# MAR.net
KiCad netlist of a schematic drawn in EAGLE
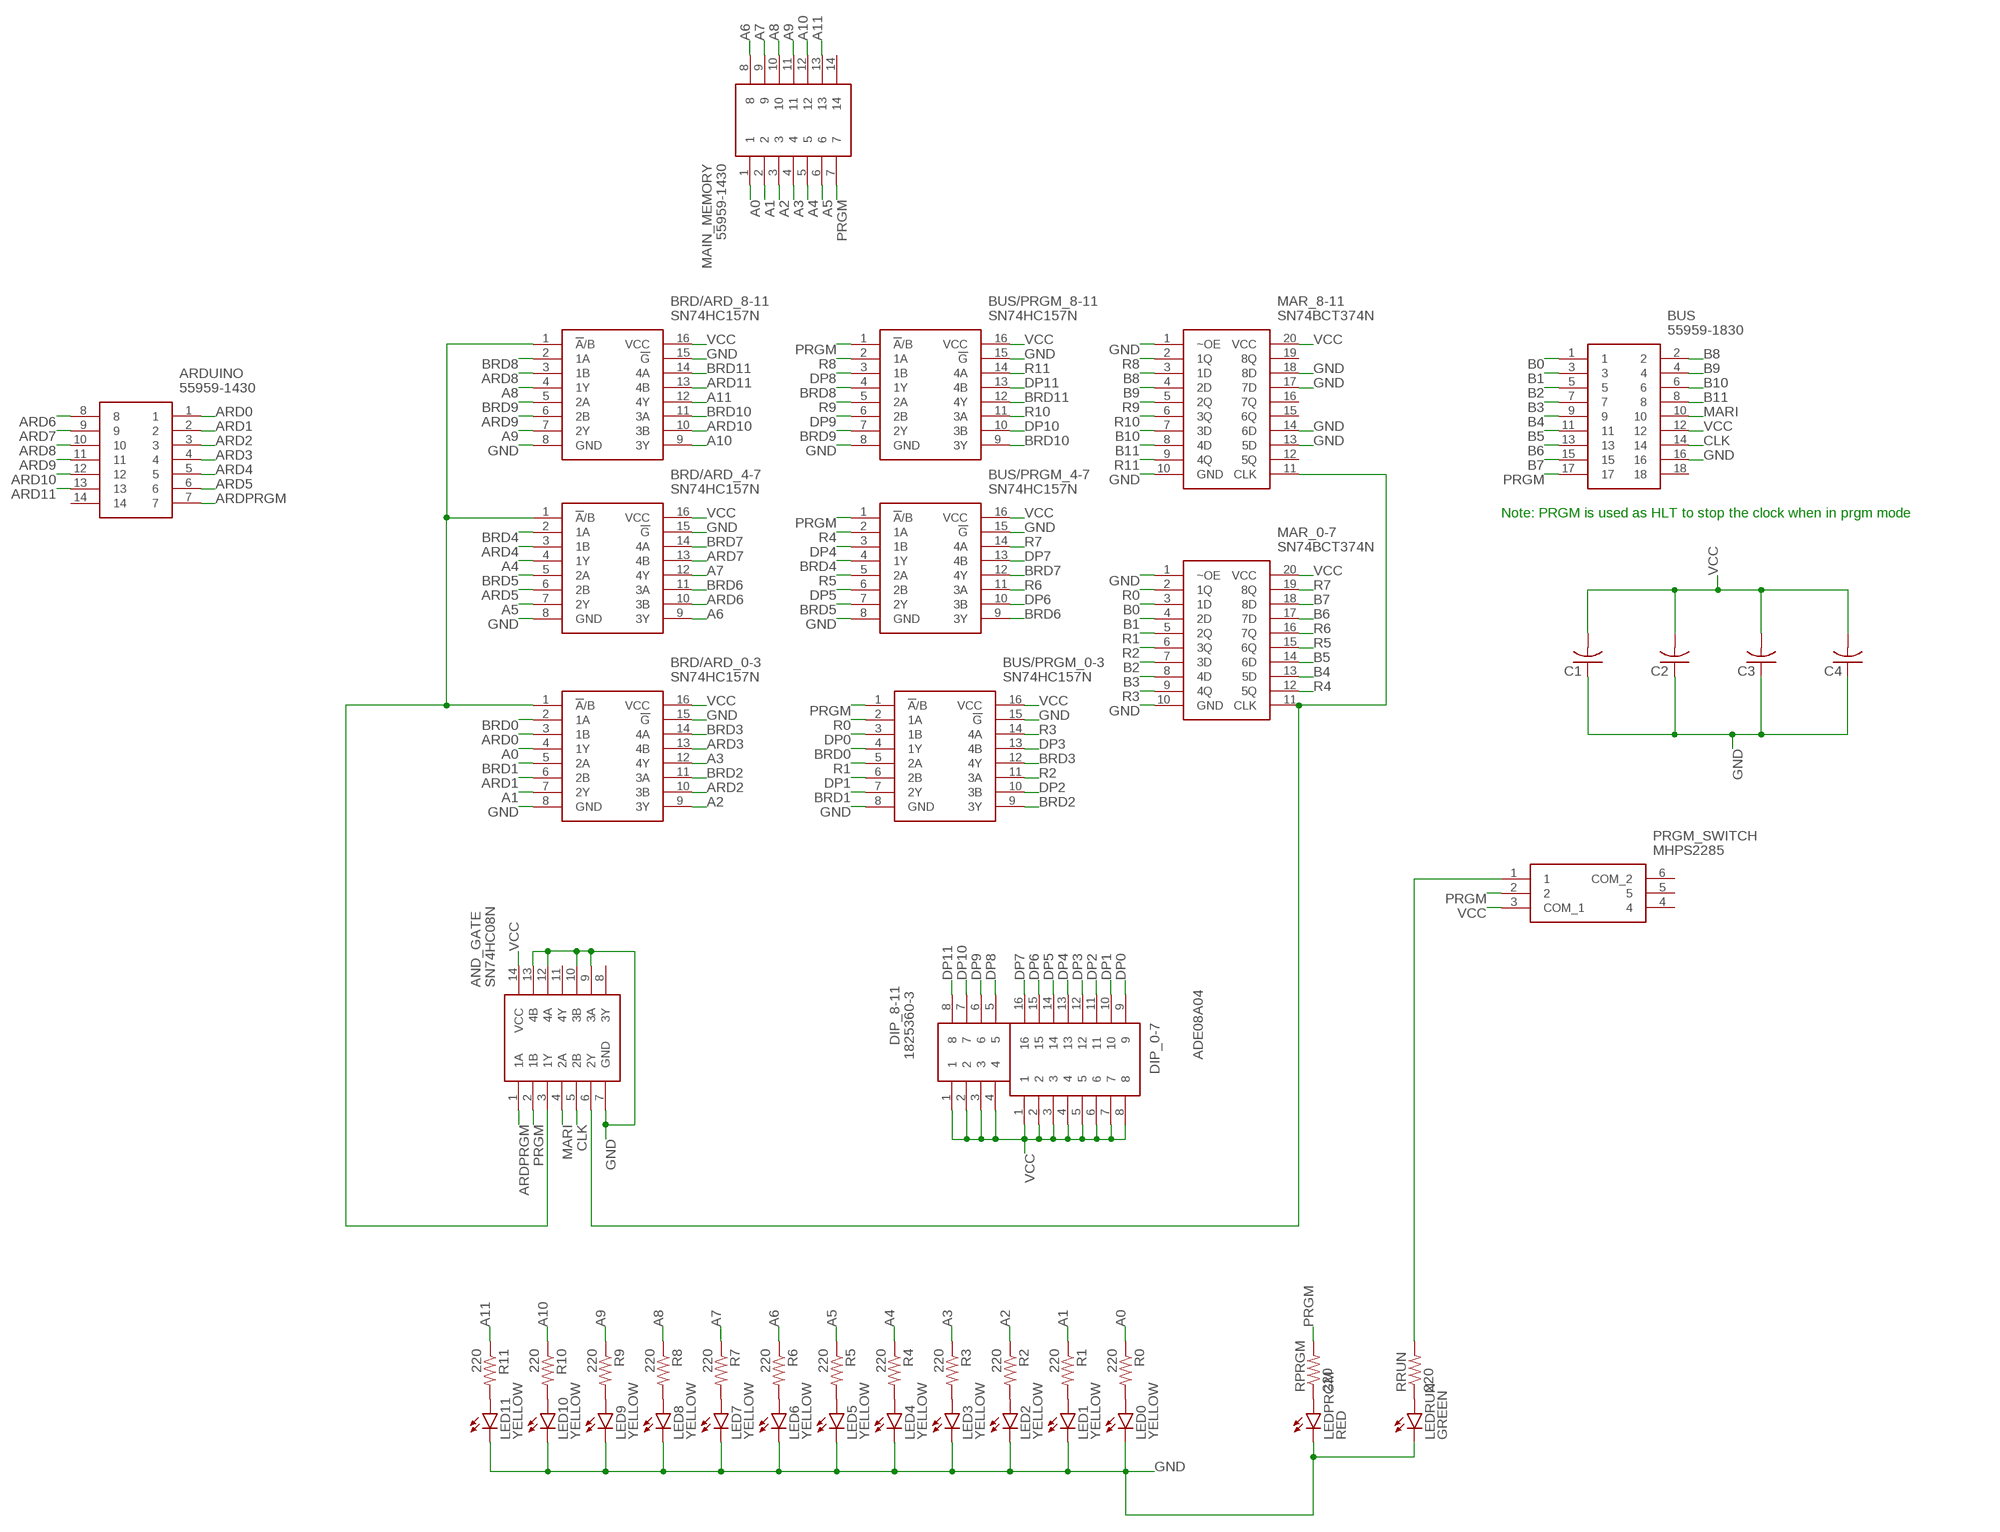
[diagram p0: schematic, sheet 1]

(export (version "E")
  (design (tool "Eeschema 10.0.6"))
  (components
    (comp (ref "AND_GATE")
      (value "SN74HC08N")
      (footprint "eagle-import:DIP794W53P254L1930H508Q14N")
      (fields (field (name "MOUSER_PART_NUMBER") "595-SN74HC08N"))
      (libsource (lib "eagle-import") (part "SN74HC08N"))
    )
    (comp (ref "ARDUINO")
      (value "55959-1430")
      (footprint "eagle-import:559591430")
      (fields (field (name "MOUSER_PART_NUMBER") "538-55959-1430"))
      (libsource (lib "eagle-import") (part "55959-1430"))
    )
    (comp (ref "BRD/ARD_0-3")
      (value "SN74HC157N")
      (footprint "eagle-import:DIP794W53P254L1930H508Q16N")
      (fields (field (name "MOUSER_PART_NUMBER") "595-SN74HC157N"))
      (libsource (lib "eagle-import") (part "SN74HC157N"))
    )
    (comp (ref "BRD/ARD_4-7")
      (value "SN74HC157N")
      (footprint "eagle-import:DIP794W53P254L1930H508Q16N")
      (fields (field (name "MOUSER_PART_NUMBER") "595-SN74HC157N"))
      (libsource (lib "eagle-import") (part "SN74HC157N"))
    )
    (comp (ref "BRD/ARD_8-11")
      (value "SN74HC157N")
      (footprint "eagle-import:DIP794W53P254L1930H508Q16N")
      (fields (field (name "MOUSER_PART_NUMBER") "595-SN74HC157N"))
      (libsource (lib "eagle-import") (part "SN74HC157N"))
    )
    (comp (ref "BUS")
      (value "55959-1830")
      (footprint "eagle-import:SHDR18W65P250X200_2X9_2140X140")
      (fields (field (name "MOUSER_PART_NUMBER") "538-55959-1830"))
      (libsource (lib "eagle-import") (part "55959-1830"))
    )
    (comp (ref "BUS/PRGM_0-3")
      (value "SN74HC157N")
      (footprint "eagle-import:DIP794W53P254L1930H508Q16N")
      (fields (field (name "MOUSER_PART_NUMBER") "595-SN74HC157N"))
      (libsource (lib "eagle-import") (part "SN74HC157N"))
    )
    (comp (ref "BUS/PRGM_4-7")
      (value "SN74HC157N")
      (footprint "eagle-import:DIP794W53P254L1930H508Q16N")
      (fields (field (name "MOUSER_PART_NUMBER") "595-SN74HC157N"))
      (libsource (lib "eagle-import") (part "SN74HC157N"))
    )
    (comp (ref "BUS/PRGM_8-11")
      (value "SN74HC157N")
      (footprint "eagle-import:DIP794W53P254L1930H508Q16N")
      (fields (field (name "MOUSER_PART_NUMBER") "595-SN74HC157N"))
      (libsource (lib "eagle-import") (part "SN74HC157N"))
    )
    (comp (ref "C1")
      (value "C-US025-024X044")
      (footprint "eagle-import:C025-024X044")
      (libsource (lib "eagle-import") (part "C-US025-024X044"))
    )
    (comp (ref "C2")
      (value "C-US025-024X044")
      (footprint "eagle-import:C025-024X044")
      (libsource (lib "eagle-import") (part "C-US025-024X044"))
    )
    (comp (ref "C3")
      (value "C-US025-024X044")
      (footprint "eagle-import:C025-024X044")
      (libsource (lib "eagle-import") (part "C-US025-024X044"))
    )
    (comp (ref "C4")
      (value "C-US025-024X044")
      (footprint "eagle-import:C025-024X044")
      (libsource (lib "eagle-import") (part "C-US025-024X044"))
    )
    (comp (ref "DIP_0-7")
      (value "ADE08A04")
      (footprint "eagle-import:DIP810W60P254L2225H590Q16N")
      (fields (field (name "MOUSER_PART_NUMBER") "506-ADE08A04"))
      (libsource (lib "eagle-import") (part "ADE08A04"))
    )
    (comp (ref "DIP_8-11")
      (value "1825360-3")
      (footprint "eagle-import:DIP813W61P254L1209H351Q8N")
      (fields (field (name "MOUSER_PART_NUMBER") "506-1825360-3"))
      (libsource (lib "eagle-import") (part "1825360-3"))
    )
    (comp (ref "LED0")
      (value "YELLOW")
      (footprint "eagle-import:LED3MM")
      (libsource (lib "eagle-import") (part "LED3MM"))
    )
    (comp (ref "LED1")
      (value "YELLOW")
      (footprint "eagle-import:LED3MM")
      (libsource (lib "eagle-import") (part "LED3MM"))
    )
    (comp (ref "LED2")
      (value "YELLOW")
      (footprint "eagle-import:LED3MM")
      (libsource (lib "eagle-import") (part "LED3MM"))
    )
    (comp (ref "LED3")
      (value "YELLOW")
      (footprint "eagle-import:LED3MM")
      (libsource (lib "eagle-import") (part "LED3MM"))
    )
    (comp (ref "LED4")
      (value "YELLOW")
      (footprint "eagle-import:LED3MM")
      (libsource (lib "eagle-import") (part "LED3MM"))
    )
    (comp (ref "LED5")
      (value "YELLOW")
      (footprint "eagle-import:LED3MM")
      (libsource (lib "eagle-import") (part "LED3MM"))
    )
    (comp (ref "LED6")
      (value "YELLOW")
      (footprint "eagle-import:LED3MM")
      (libsource (lib "eagle-import") (part "LED3MM"))
    )
    (comp (ref "LED7")
      (value "YELLOW")
      (footprint "eagle-import:LED3MM")
      (libsource (lib "eagle-import") (part "LED3MM"))
    )
    (comp (ref "LED8")
      (value "YELLOW")
      (footprint "eagle-import:LED3MM")
      (libsource (lib "eagle-import") (part "LED3MM"))
    )
    (comp (ref "LED9")
      (value "YELLOW")
      (footprint "eagle-import:LED3MM")
      (libsource (lib "eagle-import") (part "LED3MM"))
    )
    (comp (ref "LED10")
      (value "YELLOW")
      (footprint "eagle-import:LED3MM")
      (libsource (lib "eagle-import") (part "LED3MM"))
    )
    (comp (ref "LED11")
      (value "YELLOW")
      (footprint "eagle-import:LED3MM")
      (libsource (lib "eagle-import") (part "LED3MM"))
    )
    (comp (ref "LEDPRGM")
      (value "RED")
      (footprint "eagle-import:LED3MM")
      (libsource (lib "eagle-import") (part "LED3MM"))
    )
    (comp (ref "LEDRUN")
      (value "GREEN")
      (footprint "eagle-import:LED3MM")
      (libsource (lib "eagle-import") (part "LED3MM"))
    )
    (comp (ref "MAIN_MEMORY")
      (value "55959-1430")
      (footprint "eagle-import:559591430")
      (fields (field (name "MOUSER_PART_NUMBER") "538-55959-1430"))
      (libsource (lib "eagle-import") (part "55959-1430"))
    )
    (comp (ref "MAR_0-7")
      (value "SN74BCT374N")
      (footprint "eagle-import:DIP254P762X508-20")
      (fields (field (name "MOUSER_PART_NUMBER") "595-SN74BCT374N"))
      (libsource (lib "eagle-import") (part "SN74BCT374N"))
    )
    (comp (ref "MAR_8-11")
      (value "SN74BCT374N")
      (footprint "eagle-import:DIP254P762X508-20")
      (fields (field (name "MOUSER_PART_NUMBER") "595-SN74BCT374N"))
      (libsource (lib "eagle-import") (part "SN74BCT374N"))
    )
    (comp (ref "PRGM_SWITCH")
      (value "MHPS2285")
      (footprint "eagle-import:MHPS2285")
      (fields (field (name "MOUSER_PART_NUMBER") "642-MHPS2285"))
      (libsource (lib "eagle-import") (part "MHPS2285"))
    )
    (comp (ref "R0")
      (value "220")
      (footprint "eagle-import:0204_7")
      (libsource (lib "eagle-import") (part "R-US_0204/7"))
    )
    (comp (ref "R1")
      (value "220")
      (footprint "eagle-import:0204_7")
      (libsource (lib "eagle-import") (part "R-US_0204/7"))
    )
    (comp (ref "R2")
      (value "220")
      (footprint "eagle-import:0204_7")
      (libsource (lib "eagle-import") (part "R-US_0204/7"))
    )
    (comp (ref "R3")
      (value "220")
      (footprint "eagle-import:0204_7")
      (libsource (lib "eagle-import") (part "R-US_0204/7"))
    )
    (comp (ref "R4")
      (value "220")
      (footprint "eagle-import:0204_7")
      (libsource (lib "eagle-import") (part "R-US_0204/7"))
    )
    (comp (ref "R5")
      (value "220")
      (footprint "eagle-import:0204_7")
      (libsource (lib "eagle-import") (part "R-US_0204/7"))
    )
    (comp (ref "R6")
      (value "220")
      (footprint "eagle-import:0204_7")
      (libsource (lib "eagle-import") (part "R-US_0204/7"))
    )
    (comp (ref "R7")
      (value "220")
      (footprint "eagle-import:0204_7")
      (libsource (lib "eagle-import") (part "R-US_0204/7"))
    )
    (comp (ref "R8")
      (value "220")
      (footprint "eagle-import:0204_7")
      (libsource (lib "eagle-import") (part "R-US_0204/7"))
    )
    (comp (ref "R9")
      (value "220")
      (footprint "eagle-import:0204_7")
      (libsource (lib "eagle-import") (part "R-US_0204/7"))
    )
    (comp (ref "R10")
      (value "220")
      (footprint "eagle-import:0204_7")
      (libsource (lib "eagle-import") (part "R-US_0204/7"))
    )
    (comp (ref "R11")
      (value "220")
      (footprint "eagle-import:0204_7")
      (libsource (lib "eagle-import") (part "R-US_0204/7"))
    )
    (comp (ref "RPRGM")
      (value "220")
      (footprint "eagle-import:0204_7")
      (libsource (lib "eagle-import") (part "R-US_0204/7"))
    )
    (comp (ref "RRUN")
      (value "220")
      (footprint "eagle-import:0204_7")
      (libsource (lib "eagle-import") (part "R-US_0204/7"))
    )
  )
  (nets
    (net (code "1") (name "/A0") (class "Default")
      (node (ref "BRD/ARD_0-3") (pin "4") (pinfunction "1Y_4") (pintype "bidirectional"))
      (node (ref "MAIN_MEMORY") (pin "1") (pinfunction "1_1") (pintype "bidirectional"))
      (node (ref "R0") (pin "1") (pinfunction "1_1") (pintype "passive"))
    )
    (net (code "2") (name "/A1") (class "Default")
      (node (ref "BRD/ARD_0-3") (pin "7") (pinfunction "2Y_7") (pintype "bidirectional"))
      (node (ref "MAIN_MEMORY") (pin "2") (pinfunction "2_2") (pintype "bidirectional"))
      (node (ref "R1") (pin "1") (pinfunction "1_1") (pintype "passive"))
    )
    (net (code "3") (name "/A2") (class "Default")
      (node (ref "BRD/ARD_0-3") (pin "9") (pinfunction "3Y_9") (pintype "bidirectional"))
      (node (ref "MAIN_MEMORY") (pin "3") (pinfunction "3_3") (pintype "bidirectional"))
      (node (ref "R2") (pin "1") (pinfunction "1_1") (pintype "passive"))
    )
    (net (code "4") (name "/A3") (class "Default")
      (node (ref "BRD/ARD_0-3") (pin "12") (pinfunction "4Y_12") (pintype "bidirectional"))
      (node (ref "MAIN_MEMORY") (pin "4") (pinfunction "4_4") (pintype "bidirectional"))
      (node (ref "R3") (pin "1") (pinfunction "1_1") (pintype "passive"))
    )
    (net (code "5") (name "/A4") (class "Default")
      (node (ref "BRD/ARD_4-7") (pin "4") (pinfunction "1Y_4") (pintype "bidirectional"))
      (node (ref "MAIN_MEMORY") (pin "5") (pinfunction "5_5") (pintype "bidirectional"))
      (node (ref "R4") (pin "1") (pinfunction "1_1") (pintype "passive"))
    )
    (net (code "6") (name "/A5") (class "Default")
      (node (ref "BRD/ARD_4-7") (pin "7") (pinfunction "2Y_7") (pintype "bidirectional"))
      (node (ref "MAIN_MEMORY") (pin "6") (pinfunction "6_6") (pintype "bidirectional"))
      (node (ref "R5") (pin "1") (pinfunction "1_1") (pintype "passive"))
    )
    (net (code "7") (name "/A6") (class "Default")
      (node (ref "BRD/ARD_4-7") (pin "9") (pinfunction "3Y_9") (pintype "bidirectional"))
      (node (ref "MAIN_MEMORY") (pin "8") (pinfunction "8_8") (pintype "bidirectional"))
      (node (ref "R6") (pin "1") (pinfunction "1_1") (pintype "passive"))
    )
    (net (code "8") (name "/A7") (class "Default")
      (node (ref "BRD/ARD_4-7") (pin "12") (pinfunction "4Y_12") (pintype "bidirectional"))
      (node (ref "MAIN_MEMORY") (pin "9") (pinfunction "9_9") (pintype "bidirectional"))
      (node (ref "R7") (pin "1") (pinfunction "1_1") (pintype "passive"))
    )
    (net (code "9") (name "/A8") (class "Default")
      (node (ref "BRD/ARD_8-11") (pin "4") (pinfunction "1Y_4") (pintype "bidirectional"))
      (node (ref "MAIN_MEMORY") (pin "10") (pinfunction "10_10") (pintype "bidirectional"))
      (node (ref "R8") (pin "1") (pinfunction "1_1") (pintype "passive"))
    )
    (net (code "10") (name "/A9") (class "Default")
      (node (ref "BRD/ARD_8-11") (pin "7") (pinfunction "2Y_7") (pintype "bidirectional"))
      (node (ref "MAIN_MEMORY") (pin "11") (pinfunction "11_11") (pintype "bidirectional"))
      (node (ref "R9") (pin "1") (pinfunction "1_1") (pintype "passive"))
    )
    (net (code "11") (name "/A10") (class "Default")
      (node (ref "BRD/ARD_8-11") (pin "9") (pinfunction "3Y_9") (pintype "bidirectional"))
      (node (ref "MAIN_MEMORY") (pin "12") (pinfunction "12_12") (pintype "bidirectional"))
      (node (ref "R10") (pin "1") (pinfunction "1_1") (pintype "passive"))
    )
    (net (code "12") (name "/A11") (class "Default")
      (node (ref "BRD/ARD_8-11") (pin "12") (pinfunction "4Y_12") (pintype "bidirectional"))
      (node (ref "MAIN_MEMORY") (pin "13") (pinfunction "13_13") (pintype "bidirectional"))
      (node (ref "R11") (pin "1") (pinfunction "1_1") (pintype "passive"))
    )
    (net (code "13") (name "/ARD0") (class "Default")
      (node (ref "ARDUINO") (pin "1") (pinfunction "1_1") (pintype "bidirectional"))
      (node (ref "BRD/ARD_0-3") (pin "3") (pinfunction "1B_3") (pintype "bidirectional"))
    )
    (net (code "14") (name "/ARD1") (class "Default")
      (node (ref "ARDUINO") (pin "2") (pinfunction "2_2") (pintype "bidirectional"))
      (node (ref "BRD/ARD_0-3") (pin "6") (pinfunction "2B_6") (pintype "bidirectional"))
    )
    (net (code "15") (name "/ARD2") (class "Default")
      (node (ref "ARDUINO") (pin "3") (pinfunction "3_3") (pintype "bidirectional"))
      (node (ref "BRD/ARD_0-3") (pin "10") (pinfunction "3B_10") (pintype "bidirectional"))
    )
    (net (code "16") (name "/ARD3") (class "Default")
      (node (ref "ARDUINO") (pin "4") (pinfunction "4_4") (pintype "bidirectional"))
      (node (ref "BRD/ARD_0-3") (pin "13") (pinfunction "4B_13") (pintype "bidirectional"))
    )
    (net (code "17") (name "/ARD4") (class "Default")
      (node (ref "ARDUINO") (pin "5") (pinfunction "5_5") (pintype "bidirectional"))
      (node (ref "BRD/ARD_4-7") (pin "3") (pinfunction "1B_3") (pintype "bidirectional"))
    )
    (net (code "18") (name "/ARD5") (class "Default")
      (node (ref "ARDUINO") (pin "6") (pinfunction "6_6") (pintype "bidirectional"))
      (node (ref "BRD/ARD_4-7") (pin "6") (pinfunction "2B_6") (pintype "bidirectional"))
    )
    (net (code "19") (name "/ARD6") (class "Default")
      (node (ref "ARDUINO") (pin "8") (pinfunction "8_8") (pintype "bidirectional"))
      (node (ref "BRD/ARD_4-7") (pin "10") (pinfunction "3B_10") (pintype "bidirectional"))
    )
    (net (code "20") (name "/ARD7") (class "Default")
      (node (ref "ARDUINO") (pin "9") (pinfunction "9_9") (pintype "bidirectional"))
      (node (ref "BRD/ARD_4-7") (pin "13") (pinfunction "4B_13") (pintype "bidirectional"))
    )
    (net (code "21") (name "/ARD8") (class "Default")
      (node (ref "ARDUINO") (pin "10") (pinfunction "10_10") (pintype "bidirectional"))
      (node (ref "BRD/ARD_8-11") (pin "3") (pinfunction "1B_3") (pintype "bidirectional"))
    )
    (net (code "22") (name "/ARD9") (class "Default")
      (node (ref "ARDUINO") (pin "11") (pinfunction "11_11") (pintype "bidirectional"))
      (node (ref "BRD/ARD_8-11") (pin "6") (pinfunction "2B_6") (pintype "bidirectional"))
    )
    (net (code "23") (name "/ARD10") (class "Default")
      (node (ref "ARDUINO") (pin "12") (pinfunction "12_12") (pintype "bidirectional"))
      (node (ref "BRD/ARD_8-11") (pin "10") (pinfunction "3B_10") (pintype "bidirectional"))
    )
    (net (code "24") (name "/ARD11") (class "Default")
      (node (ref "ARDUINO") (pin "13") (pinfunction "13_13") (pintype "bidirectional"))
      (node (ref "BRD/ARD_8-11") (pin "13") (pinfunction "4B_13") (pintype "bidirectional"))
    )
    (net (code "25") (name "/ARDPRGM") (class "Default")
      (node (ref "AND_GATE") (pin "1") (pinfunction "1A_1") (pintype "bidirectional"))
      (node (ref "ARDUINO") (pin "7") (pinfunction "7_7") (pintype "bidirectional"))
    )
    (net (code "26") (name "/B0") (class "Default")
      (node (ref "BUS") (pin "1") (pinfunction "1_1") (pintype "bidirectional"))
      (node (ref "MAR_0-7") (pin "3") (pinfunction "1D_3") (pintype "bidirectional"))
    )
    (net (code "27") (name "/B1") (class "Default")
      (node (ref "BUS") (pin "3") (pinfunction "3_3") (pintype "bidirectional"))
      (node (ref "MAR_0-7") (pin "4") (pinfunction "2D_4") (pintype "bidirectional"))
    )
    (net (code "28") (name "/B2") (class "Default")
      (node (ref "BUS") (pin "5") (pinfunction "5_5") (pintype "bidirectional"))
      (node (ref "MAR_0-7") (pin "7") (pinfunction "3D_7") (pintype "bidirectional"))
    )
    (net (code "29") (name "/B3") (class "Default")
      (node (ref "BUS") (pin "7") (pinfunction "7_7") (pintype "bidirectional"))
      (node (ref "MAR_0-7") (pin "8") (pinfunction "4D_8") (pintype "bidirectional"))
    )
    (net (code "30") (name "/B4") (class "Default")
      (node (ref "BUS") (pin "9") (pinfunction "9_9") (pintype "bidirectional"))
      (node (ref "MAR_0-7") (pin "13") (pinfunction "5D_13") (pintype "bidirectional"))
    )
    (net (code "31") (name "/B5") (class "Default")
      (node (ref "BUS") (pin "11") (pinfunction "11_11") (pintype "bidirectional"))
      (node (ref "MAR_0-7") (pin "14") (pinfunction "6D_14") (pintype "bidirectional"))
    )
    (net (code "32") (name "/B6") (class "Default")
      (node (ref "BUS") (pin "13") (pinfunction "13_13") (pintype "bidirectional"))
      (node (ref "MAR_0-7") (pin "17") (pinfunction "7D_17") (pintype "bidirectional"))
    )
    (net (code "33") (name "/B7") (class "Default")
      (node (ref "BUS") (pin "15") (pinfunction "15_15") (pintype "bidirectional"))
      (node (ref "MAR_0-7") (pin "18") (pinfunction "8D_18") (pintype "bidirectional"))
    )
    (net (code "34") (name "/B8") (class "Default")
      (node (ref "BUS") (pin "2") (pinfunction "2_2") (pintype "bidirectional"))
      (node (ref "MAR_8-11") (pin "3") (pinfunction "1D_3") (pintype "bidirectional"))
    )
    (net (code "35") (name "/B9") (class "Default")
      (node (ref "BUS") (pin "4") (pinfunction "4_4") (pintype "bidirectional"))
      (node (ref "MAR_8-11") (pin "4") (pinfunction "2D_4") (pintype "bidirectional"))
    )
    (net (code "36") (name "/B10") (class "Default")
      (node (ref "BUS") (pin "6") (pinfunction "6_6") (pintype "bidirectional"))
      (node (ref "MAR_8-11") (pin "7") (pinfunction "3D_7") (pintype "bidirectional"))
    )
    (net (code "37") (name "/B11") (class "Default")
      (node (ref "BUS") (pin "8") (pinfunction "8_8") (pintype "bidirectional"))
      (node (ref "MAR_8-11") (pin "8") (pinfunction "4D_8") (pintype "bidirectional"))
    )
    (net (code "38") (name "/BRD0") (class "Default")
      (node (ref "BRD/ARD_0-3") (pin "2") (pinfunction "1A_2") (pintype "bidirectional"))
      (node (ref "BUS/PRGM_0-3") (pin "4") (pinfunction "1Y_4") (pintype "bidirectional"))
    )
    (net (code "39") (name "/BRD1") (class "Default")
      (node (ref "BRD/ARD_0-3") (pin "5") (pinfunction "2A_5") (pintype "bidirectional"))
      (node (ref "BUS/PRGM_0-3") (pin "7") (pinfunction "2Y_7") (pintype "bidirectional"))
    )
    (net (code "40") (name "/BRD2") (class "Default")
      (node (ref "BRD/ARD_0-3") (pin "11") (pinfunction "3A_11") (pintype "bidirectional"))
      (node (ref "BUS/PRGM_0-3") (pin "9") (pinfunction "3Y_9") (pintype "bidirectional"))
    )
    (net (code "41") (name "/BRD3") (class "Default")
      (node (ref "BRD/ARD_0-3") (pin "14") (pinfunction "4A_14") (pintype "bidirectional"))
      (node (ref "BUS/PRGM_0-3") (pin "12") (pinfunction "4Y_12") (pintype "bidirectional"))
    )
    (net (code "42") (name "/BRD4") (class "Default")
      (node (ref "BRD/ARD_4-7") (pin "2") (pinfunction "1A_2") (pintype "bidirectional"))
      (node (ref "BUS/PRGM_4-7") (pin "4") (pinfunction "1Y_4") (pintype "bidirectional"))
    )
    (net (code "43") (name "/BRD5") (class "Default")
      (node (ref "BRD/ARD_4-7") (pin "5") (pinfunction "2A_5") (pintype "bidirectional"))
      (node (ref "BUS/PRGM_4-7") (pin "7") (pinfunction "2Y_7") (pintype "bidirectional"))
    )
    (net (code "44") (name "/BRD6") (class "Default")
      (node (ref "BRD/ARD_4-7") (pin "11") (pinfunction "3A_11") (pintype "bidirectional"))
      (node (ref "BUS/PRGM_4-7") (pin "9") (pinfunction "3Y_9") (pintype "bidirectional"))
    )
    (net (code "45") (name "/BRD7") (class "Default")
      (node (ref "BRD/ARD_4-7") (pin "14") (pinfunction "4A_14") (pintype "bidirectional"))
      (node (ref "BUS/PRGM_4-7") (pin "12") (pinfunction "4Y_12") (pintype "bidirectional"))
    )
    (net (code "46") (name "/BRD8") (class "Default")
      (node (ref "BRD/ARD_8-11") (pin "2") (pinfunction "1A_2") (pintype "bidirectional"))
      (node (ref "BUS/PRGM_8-11") (pin "4") (pinfunction "1Y_4") (pintype "bidirectional"))
    )
    (net (code "47") (name "/BRD9") (class "Default")
      (node (ref "BRD/ARD_8-11") (pin "5") (pinfunction "2A_5") (pintype "bidirectional"))
      (node (ref "BUS/PRGM_8-11") (pin "7") (pinfunction "2Y_7") (pintype "bidirectional"))
    )
    (net (code "48") (name "/BRD10") (class "Default")
      (node (ref "BRD/ARD_8-11") (pin "11") (pinfunction "3A_11") (pintype "bidirectional"))
      (node (ref "BUS/PRGM_8-11") (pin "9") (pinfunction "3Y_9") (pintype "bidirectional"))
    )
    (net (code "49") (name "/BRD11") (class "Default")
      (node (ref "BRD/ARD_8-11") (pin "14") (pinfunction "4A_14") (pintype "bidirectional"))
      (node (ref "BUS/PRGM_8-11") (pin "12") (pinfunction "4Y_12") (pintype "bidirectional"))
    )
    (net (code "50") (name "/CLK") (class "Default")
      (node (ref "AND_GATE") (pin "5") (pinfunction "2B_5") (pintype "bidirectional"))
      (node (ref "BUS") (pin "14") (pinfunction "14_14") (pintype "bidirectional"))
    )
    (net (code "51") (name "/DP0") (class "Default")
      (node (ref "BUS/PRGM_0-3") (pin "3") (pinfunction "1B_3") (pintype "bidirectional"))
      (node (ref "DIP_0-7") (pin "9") (pinfunction "9_9") (pintype "bidirectional"))
    )
    (net (code "52") (name "/DP1") (class "Default")
      (node (ref "BUS/PRGM_0-3") (pin "6") (pinfunction "2B_6") (pintype "bidirectional"))
      (node (ref "DIP_0-7") (pin "10") (pinfunction "10_10") (pintype "bidirectional"))
    )
    (net (code "53") (name "/DP2") (class "Default")
      (node (ref "BUS/PRGM_0-3") (pin "10") (pinfunction "3B_10") (pintype "bidirectional"))
      (node (ref "DIP_0-7") (pin "11") (pinfunction "11_11") (pintype "bidirectional"))
    )
    (net (code "54") (name "/DP3") (class "Default")
      (node (ref "BUS/PRGM_0-3") (pin "13") (pinfunction "4B_13") (pintype "bidirectional"))
      (node (ref "DIP_0-7") (pin "12") (pinfunction "12_12") (pintype "bidirectional"))
    )
    (net (code "55") (name "/DP4") (class "Default")
      (node (ref "BUS/PRGM_4-7") (pin "3") (pinfunction "1B_3") (pintype "bidirectional"))
      (node (ref "DIP_0-7") (pin "13") (pinfunction "13_13") (pintype "bidirectional"))
    )
    (net (code "56") (name "/DP5") (class "Default")
      (node (ref "BUS/PRGM_4-7") (pin "6") (pinfunction "2B_6") (pintype "bidirectional"))
      (node (ref "DIP_0-7") (pin "14") (pinfunction "14_14") (pintype "bidirectional"))
    )
    (net (code "57") (name "/DP6") (class "Default")
      (node (ref "BUS/PRGM_4-7") (pin "10") (pinfunction "3B_10") (pintype "bidirectional"))
      (node (ref "DIP_0-7") (pin "15") (pinfunction "15_15") (pintype "bidirectional"))
    )
    (net (code "58") (name "/DP7") (class "Default")
      (node (ref "BUS/PRGM_4-7") (pin "13") (pinfunction "4B_13") (pintype "bidirectional"))
      (node (ref "DIP_0-7") (pin "16") (pinfunction "16_16") (pintype "bidirectional"))
    )
    (net (code "59") (name "/DP8") (class "Default")
      (node (ref "BUS/PRGM_8-11") (pin "3") (pinfunction "1B_3") (pintype "bidirectional"))
      (node (ref "DIP_8-11") (pin "5") (pinfunction "5_5") (pintype "bidirectional"))
    )
    (net (code "60") (name "/DP9") (class "Default")
      (node (ref "BUS/PRGM_8-11") (pin "6") (pinfunction "2B_6") (pintype "bidirectional"))
      (node (ref "DIP_8-11") (pin "6") (pinfunction "6_6") (pintype "bidirectional"))
    )
    (net (code "61") (name "/DP10") (class "Default")
      (node (ref "BUS/PRGM_8-11") (pin "10") (pinfunction "3B_10") (pintype "bidirectional"))
      (node (ref "DIP_8-11") (pin "7") (pinfunction "7_7") (pintype "bidirectional"))
    )
    (net (code "62") (name "/DP11") (class "Default")
      (node (ref "BUS/PRGM_8-11") (pin "13") (pinfunction "4B_13") (pintype "bidirectional"))
      (node (ref "DIP_8-11") (pin "8") (pinfunction "8_8") (pintype "bidirectional"))
    )
    (net (code "63") (name "/GND") (class "Default")
      (node (ref "AND_GATE") (pin "10") (pinfunction "3B_10") (pintype "bidirectional"))
      (node (ref "AND_GATE") (pin "12") (pinfunction "4A_12") (pintype "bidirectional"))
      (node (ref "AND_GATE") (pin "13") (pinfunction "4B_13") (pintype "bidirectional"))
      (node (ref "AND_GATE") (pin "7") (pinfunction "GND_7") (pintype "bidirectional"))
      (node (ref "AND_GATE") (pin "9") (pinfunction "3A_9") (pintype "bidirectional"))
      (node (ref "BRD/ARD_0-3") (pin "15") (pinfunction "~{G}_15") (pintype "bidirectional"))
      (node (ref "BRD/ARD_0-3") (pin "8") (pinfunction "GND_8") (pintype "bidirectional"))
      (node (ref "BRD/ARD_4-7") (pin "15") (pinfunction "~{G}_15") (pintype "bidirectional"))
      (node (ref "BRD/ARD_4-7") (pin "8") (pinfunction "GND_8") (pintype "bidirectional"))
      (node (ref "BRD/ARD_8-11") (pin "15") (pinfunction "~{G}_15") (pintype "bidirectional"))
      (node (ref "BRD/ARD_8-11") (pin "8") (pinfunction "GND_8") (pintype "bidirectional"))
      (node (ref "BUS") (pin "16") (pinfunction "16_16") (pintype "bidirectional"))
      (node (ref "BUS/PRGM_0-3") (pin "15") (pinfunction "~{G}_15") (pintype "bidirectional"))
      (node (ref "BUS/PRGM_0-3") (pin "8") (pinfunction "GND_8") (pintype "bidirectional"))
      (node (ref "BUS/PRGM_4-7") (pin "15") (pinfunction "~{G}_15") (pintype "bidirectional"))
      (node (ref "BUS/PRGM_4-7") (pin "8") (pinfunction "GND_8") (pintype "bidirectional"))
      (node (ref "BUS/PRGM_8-11") (pin "15") (pinfunction "~{G}_15") (pintype "bidirectional"))
      (node (ref "BUS/PRGM_8-11") (pin "8") (pinfunction "GND_8") (pintype "bidirectional"))
      (node (ref "C1") (pin "1") (pinfunction "1_1") (pintype "passive"))
      (node (ref "C2") (pin "1") (pinfunction "1_1") (pintype "passive"))
      (node (ref "C3") (pin "1") (pinfunction "1_1") (pintype "passive"))
      (node (ref "C4") (pin "1") (pinfunction "1_1") (pintype "passive"))
      (node (ref "LED0") (pin "K") (pinfunction "C_K") (pintype "passive"))
      (node (ref "LED1") (pin "K") (pinfunction "C_K") (pintype "passive"))
      (node (ref "LED10") (pin "K") (pinfunction "C_K") (pintype "passive"))
      (node (ref "LED11") (pin "K") (pinfunction "C_K") (pintype "passive"))
      (node (ref "LED2") (pin "K") (pinfunction "C_K") (pintype "passive"))
      (node (ref "LED3") (pin "K") (pinfunction "C_K") (pintype "passive"))
      (node (ref "LED4") (pin "K") (pinfunction "C_K") (pintype "passive"))
      (node (ref "LED5") (pin "K") (pinfunction "C_K") (pintype "passive"))
      (node (ref "LED6") (pin "K") (pinfunction "C_K") (pintype "passive"))
      (node (ref "LED7") (pin "K") (pinfunction "C_K") (pintype "passive"))
      (node (ref "LED8") (pin "K") (pinfunction "C_K") (pintype "passive"))
      (node (ref "LED9") (pin "K") (pinfunction "C_K") (pintype "passive"))
      (node (ref "LEDPRGM") (pin "K") (pinfunction "C_K") (pintype "passive"))
      (node (ref "LEDRUN") (pin "K") (pinfunction "C_K") (pintype "passive"))
      (node (ref "MAR_0-7") (pin "1") (pinfunction "~{OE}_1") (pintype "bidirectional"))
      (node (ref "MAR_0-7") (pin "10") (pinfunction "GND_10") (pintype "bidirectional"))
      (node (ref "MAR_8-11") (pin "1") (pinfunction "~{OE}_1") (pintype "bidirectional"))
      (node (ref "MAR_8-11") (pin "10") (pinfunction "GND_10") (pintype "bidirectional"))
      (node (ref "MAR_8-11") (pin "13") (pinfunction "5D_13") (pintype "bidirectional"))
      (node (ref "MAR_8-11") (pin "14") (pinfunction "6D_14") (pintype "bidirectional"))
      (node (ref "MAR_8-11") (pin "17") (pinfunction "7D_17") (pintype "bidirectional"))
      (node (ref "MAR_8-11") (pin "18") (pinfunction "8D_18") (pintype "bidirectional"))
    )
    (net (code "64") (name "/MARI") (class "Default")
      (node (ref "AND_GATE") (pin "4") (pinfunction "2A_4") (pintype "bidirectional"))
      (node (ref "BUS") (pin "10") (pinfunction "10_10") (pintype "bidirectional"))
    )
    (net (code "65") (name "/PRGM") (class "Default")
      (node (ref "AND_GATE") (pin "2") (pinfunction "1B_2") (pintype "bidirectional"))
      (node (ref "BUS") (pin "17") (pinfunction "17_17") (pintype "bidirectional"))
      (node (ref "BUS/PRGM_0-3") (pin "1") (pinfunction "~{A}/B_1") (pintype "bidirectional"))
      (node (ref "BUS/PRGM_4-7") (pin "1") (pinfunction "~{A}/B_1") (pintype "bidirectional"))
      (node (ref "BUS/PRGM_8-11") (pin "1") (pinfunction "~{A}/B_1") (pintype "bidirectional"))
      (node (ref "MAIN_MEMORY") (pin "7") (pinfunction "7_7") (pintype "bidirectional"))
      (node (ref "PRGM_SWITCH") (pin "2") (pinfunction "2_2") (pintype "bidirectional"))
      (node (ref "RPRGM") (pin "2") (pinfunction "2_2") (pintype "passive"))
    )
    (net (code "66") (name "/R0") (class "Default")
      (node (ref "BUS/PRGM_0-3") (pin "2") (pinfunction "1A_2") (pintype "bidirectional"))
      (node (ref "MAR_0-7") (pin "2") (pinfunction "1Q_2") (pintype "bidirectional"))
    )
    (net (code "67") (name "/R1") (class "Default")
      (node (ref "BUS/PRGM_0-3") (pin "5") (pinfunction "2A_5") (pintype "bidirectional"))
      (node (ref "MAR_0-7") (pin "5") (pinfunction "2Q_5") (pintype "bidirectional"))
    )
    (net (code "68") (name "/R2") (class "Default")
      (node (ref "BUS/PRGM_0-3") (pin "11") (pinfunction "3A_11") (pintype "bidirectional"))
      (node (ref "MAR_0-7") (pin "6") (pinfunction "3Q_6") (pintype "bidirectional"))
    )
    (net (code "69") (name "/R3") (class "Default")
      (node (ref "BUS/PRGM_0-3") (pin "14") (pinfunction "4A_14") (pintype "bidirectional"))
      (node (ref "MAR_0-7") (pin "9") (pinfunction "4Q_9") (pintype "bidirectional"))
    )
    (net (code "70") (name "/R4") (class "Default")
      (node (ref "BUS/PRGM_4-7") (pin "2") (pinfunction "1A_2") (pintype "bidirectional"))
      (node (ref "MAR_0-7") (pin "12") (pinfunction "5Q_12") (pintype "bidirectional"))
    )
    (net (code "71") (name "/R5") (class "Default")
      (node (ref "BUS/PRGM_4-7") (pin "5") (pinfunction "2A_5") (pintype "bidirectional"))
      (node (ref "MAR_0-7") (pin "15") (pinfunction "6Q_15") (pintype "bidirectional"))
    )
    (net (code "72") (name "/R6") (class "Default")
      (node (ref "BUS/PRGM_4-7") (pin "11") (pinfunction "3A_11") (pintype "bidirectional"))
      (node (ref "MAR_0-7") (pin "16") (pinfunction "7Q_16") (pintype "bidirectional"))
    )
    (net (code "73") (name "/R7") (class "Default")
      (node (ref "BUS/PRGM_4-7") (pin "14") (pinfunction "4A_14") (pintype "bidirectional"))
      (node (ref "MAR_0-7") (pin "19") (pinfunction "8Q_19") (pintype "bidirectional"))
    )
    (net (code "74") (name "/R8") (class "Default")
      (node (ref "BUS/PRGM_8-11") (pin "2") (pinfunction "1A_2") (pintype "bidirectional"))
      (node (ref "MAR_8-11") (pin "2") (pinfunction "1Q_2") (pintype "bidirectional"))
    )
    (net (code "75") (name "/R9") (class "Default")
      (node (ref "BUS/PRGM_8-11") (pin "5") (pinfunction "2A_5") (pintype "bidirectional"))
      (node (ref "MAR_8-11") (pin "5") (pinfunction "2Q_5") (pintype "bidirectional"))
    )
    (net (code "76") (name "/R10") (class "Default")
      (node (ref "BUS/PRGM_8-11") (pin "11") (pinfunction "3A_11") (pintype "bidirectional"))
      (node (ref "MAR_8-11") (pin "6") (pinfunction "3Q_6") (pintype "bidirectional"))
    )
    (net (code "77") (name "/R11") (class "Default")
      (node (ref "BUS/PRGM_8-11") (pin "14") (pinfunction "4A_14") (pintype "bidirectional"))
      (node (ref "MAR_8-11") (pin "9") (pinfunction "4Q_9") (pintype "bidirectional"))
    )
    (net (code "78") (name "/VCC") (class "Default")
      (node (ref "AND_GATE") (pin "14") (pinfunction "VCC_14") (pintype "bidirectional"))
      (node (ref "BRD/ARD_0-3") (pin "16") (pinfunction "VCC_16") (pintype "bidirectional"))
      (node (ref "BRD/ARD_4-7") (pin "16") (pinfunction "VCC_16") (pintype "bidirectional"))
      (node (ref "BRD/ARD_8-11") (pin "16") (pinfunction "VCC_16") (pintype "bidirectional"))
      (node (ref "BUS") (pin "12") (pinfunction "12_12") (pintype "bidirectional"))
      (node (ref "BUS/PRGM_0-3") (pin "16") (pinfunction "VCC_16") (pintype "bidirectional"))
      (node (ref "BUS/PRGM_4-7") (pin "16") (pinfunction "VCC_16") (pintype "bidirectional"))
      (node (ref "BUS/PRGM_8-11") (pin "16") (pinfunction "VCC_16") (pintype "bidirectional"))
      (node (ref "C1") (pin "2") (pinfunction "2_2") (pintype "passive"))
      (node (ref "C2") (pin "2") (pinfunction "2_2") (pintype "passive"))
      (node (ref "C3") (pin "2") (pinfunction "2_2") (pintype "passive"))
      (node (ref "C4") (pin "2") (pinfunction "2_2") (pintype "passive"))
      (node (ref "DIP_0-7") (pin "1") (pinfunction "1_1") (pintype "bidirectional"))
      (node (ref "DIP_0-7") (pin "2") (pinfunction "2_2") (pintype "bidirectional"))
      (node (ref "DIP_0-7") (pin "3") (pinfunction "3_3") (pintype "bidirectional"))
      (node (ref "DIP_0-7") (pin "4") (pinfunction "4_4") (pintype "bidirectional"))
      (node (ref "DIP_0-7") (pin "5") (pinfunction "5_5") (pintype "bidirectional"))
      (node (ref "DIP_0-7") (pin "6") (pinfunction "6_6") (pintype "bidirectional"))
      (node (ref "DIP_0-7") (pin "7") (pinfunction "7_7") (pintype "bidirectional"))
      (node (ref "DIP_0-7") (pin "8") (pinfunction "8_8") (pintype "bidirectional"))
      (node (ref "DIP_8-11") (pin "1") (pinfunction "1_1") (pintype "bidirectional"))
      (node (ref "DIP_8-11") (pin "2") (pinfunction "2_2") (pintype "bidirectional"))
      (node (ref "DIP_8-11") (pin "3") (pinfunction "3_3") (pintype "bidirectional"))
      (node (ref "DIP_8-11") (pin "4") (pinfunction "4_4") (pintype "bidirectional"))
      (node (ref "MAR_0-7") (pin "20") (pinfunction "VCC_20") (pintype "bidirectional"))
      (node (ref "MAR_8-11") (pin "20") (pinfunction "VCC_20") (pintype "bidirectional"))
      (node (ref "PRGM_SWITCH") (pin "3") (pinfunction "COM_1_3") (pintype "bidirectional"))
    )
    (net (code "79") (name "Net-(AND_GATE-1Y)") (class "Default")
      (node (ref "AND_GATE") (pin "3") (pinfunction "1Y_3") (pintype "bidirectional"))
      (node (ref "BRD/ARD_0-3") (pin "1") (pinfunction "~{A}/B_1") (pintype "bidirectional"))
      (node (ref "BRD/ARD_4-7") (pin "1") (pinfunction "~{A}/B_1") (pintype "bidirectional"))
      (node (ref "BRD/ARD_8-11") (pin "1") (pinfunction "~{A}/B_1") (pintype "bidirectional"))
    )
    (net (code "80") (name "Net-(AND_GATE-2Y)") (class "Default")
      (node (ref "AND_GATE") (pin "6") (pinfunction "2Y_6") (pintype "bidirectional"))
      (node (ref "MAR_0-7") (pin "11") (pinfunction "CLK_11") (pintype "bidirectional"))
      (node (ref "MAR_8-11") (pin "11") (pinfunction "CLK_11") (pintype "bidirectional"))
    )
    (net (code "81") (name "Net-(LED0-PadA)") (class "Default")
      (node (ref "LED0") (pin "A") (pinfunction "A_A") (pintype "passive"))
      (node (ref "R0") (pin "2") (pinfunction "2_2") (pintype "passive"))
    )
    (net (code "82") (name "Net-(LED1-PadA)") (class "Default")
      (node (ref "LED1") (pin "A") (pinfunction "A_A") (pintype "passive"))
      (node (ref "R1") (pin "2") (pinfunction "2_2") (pintype "passive"))
    )
    (net (code "83") (name "Net-(LED2-PadA)") (class "Default")
      (node (ref "LED2") (pin "A") (pinfunction "A_A") (pintype "passive"))
      (node (ref "R2") (pin "2") (pinfunction "2_2") (pintype "passive"))
    )
    (net (code "84") (name "Net-(LED3-PadA)") (class "Default")
      (node (ref "LED3") (pin "A") (pinfunction "A_A") (pintype "passive"))
      (node (ref "R3") (pin "2") (pinfunction "2_2") (pintype "passive"))
    )
    (net (code "85") (name "Net-(LED4-PadA)") (class "Default")
      (node (ref "LED4") (pin "A") (pinfunction "A_A") (pintype "passive"))
      (node (ref "R4") (pin "2") (pinfunction "2_2") (pintype "passive"))
    )
    (net (code "86") (name "Net-(LED5-PadA)") (class "Default")
      (node (ref "LED5") (pin "A") (pinfunction "A_A") (pintype "passive"))
      (node (ref "R5") (pin "2") (pinfunction "2_2") (pintype "passive"))
    )
    (net (code "87") (name "Net-(LED6-PadA)") (class "Default")
      (node (ref "LED6") (pin "A") (pinfunction "A_A") (pintype "passive"))
      (node (ref "R6") (pin "2") (pinfunction "2_2") (pintype "passive"))
    )
    (net (code "88") (name "Net-(LED7-PadA)") (class "Default")
      (node (ref "LED7") (pin "A") (pinfunction "A_A") (pintype "passive"))
      (node (ref "R7") (pin "2") (pinfunction "2_2") (pintype "passive"))
    )
    (net (code "89") (name "Net-(LED8-PadA)") (class "Default")
      (node (ref "LED8") (pin "A") (pinfunction "A_A") (pintype "passive"))
      (node (ref "R8") (pin "2") (pinfunction "2_2") (pintype "passive"))
    )
    (net (code "90") (name "Net-(LED9-PadA)") (class "Default")
      (node (ref "LED9") (pin "A") (pinfunction "A_A") (pintype "passive"))
      (node (ref "R9") (pin "2") (pinfunction "2_2") (pintype "passive"))
    )
    (net (code "91") (name "Net-(LED10-PadA)") (class "Default")
      (node (ref "LED10") (pin "A") (pinfunction "A_A") (pintype "passive"))
      (node (ref "R10") (pin "2") (pinfunction "2_2") (pintype "passive"))
    )
    (net (code "92") (name "Net-(LED11-PadA)") (class "Default")
      (node (ref "LED11") (pin "A") (pinfunction "A_A") (pintype "passive"))
      (node (ref "R11") (pin "2") (pinfunction "2_2") (pintype "passive"))
    )
    (net (code "93") (name "Net-(LEDPRGM-PadA)") (class "Default")
      (node (ref "LEDPRGM") (pin "A") (pinfunction "A_A") (pintype "passive"))
      (node (ref "RPRGM") (pin "1") (pinfunction "1_1") (pintype "passive"))
    )
    (net (code "94") (name "Net-(LEDRUN-PadA)") (class "Default")
      (node (ref "LEDRUN") (pin "A") (pinfunction "A_A") (pintype "passive"))
      (node (ref "RRUN") (pin "1") (pinfunction "1_1") (pintype "passive"))
    )
    (net (code "95") (name "Net-(PRGM_SWITCH-Pad1)") (class "Default")
      (node (ref "PRGM_SWITCH") (pin "1") (pinfunction "1_1") (pintype "bidirectional"))
      (node (ref "RRUN") (pin "2") (pinfunction "2_2") (pintype "passive"))
    )
    (net (code "96") (name "unconnected-(AND_GATE-3Y-Pad8)") (class "Default")
      (node (ref "AND_GATE") (pin "8") (pinfunction "3Y_8") (pintype "bidirectional"))
    )
    (net (code "97") (name "unconnected-(AND_GATE-4Y-Pad11)") (class "Default")
      (node (ref "AND_GATE") (pin "11") (pinfunction "4Y_11") (pintype "bidirectional"))
    )
    (net (code "98") (name "unconnected-(ARDUINO-Pad14)") (class "Default")
      (node (ref "ARDUINO") (pin "14") (pinfunction "14_14") (pintype "bidirectional"))
    )
    (net (code "99") (name "unconnected-(BUS-Pad18)") (class "Default")
      (node (ref "BUS") (pin "18") (pinfunction "18_18") (pintype "bidirectional"))
    )
    (net (code "100") (name "unconnected-(MAIN_MEMORY-Pad14)") (class "Default")
      (node (ref "MAIN_MEMORY") (pin "14") (pinfunction "14_14") (pintype "bidirectional"))
    )
    (net (code "101") (name "unconnected-(MAR_8-11-5Q-Pad12)") (class "Default")
      (node (ref "MAR_8-11") (pin "12") (pinfunction "5Q_12") (pintype "bidirectional"))
    )
    (net (code "102") (name "unconnected-(MAR_8-11-6Q-Pad15)") (class "Default")
      (node (ref "MAR_8-11") (pin "15") (pinfunction "6Q_15") (pintype "bidirectional"))
    )
    (net (code "103") (name "unconnected-(MAR_8-11-7Q-Pad16)") (class "Default")
      (node (ref "MAR_8-11") (pin "16") (pinfunction "7Q_16") (pintype "bidirectional"))
    )
    (net (code "104") (name "unconnected-(MAR_8-11-8Q-Pad19)") (class "Default")
      (node (ref "MAR_8-11") (pin "19") (pinfunction "8Q_19") (pintype "bidirectional"))
    )
    (net (code "105") (name "unconnected-(PRGM_SWITCH-COM_2-Pad6)") (class "Default")
      (node (ref "PRGM_SWITCH") (pin "6") (pinfunction "COM_2_6") (pintype "bidirectional"))
    )
    (net (code "106") (name "unconnected-(PRGM_SWITCH-Pad4)") (class "Default")
      (node (ref "PRGM_SWITCH") (pin "4") (pinfunction "4_4") (pintype "bidirectional"))
    )
    (net (code "107") (name "unconnected-(PRGM_SWITCH-Pad5)") (class "Default")
      (node (ref "PRGM_SWITCH") (pin "5") (pinfunction "5_5") (pintype "bidirectional"))
    )
  )
)
